# SP3485.net
KiCad netlist of a schematic drawn in Altium Designer
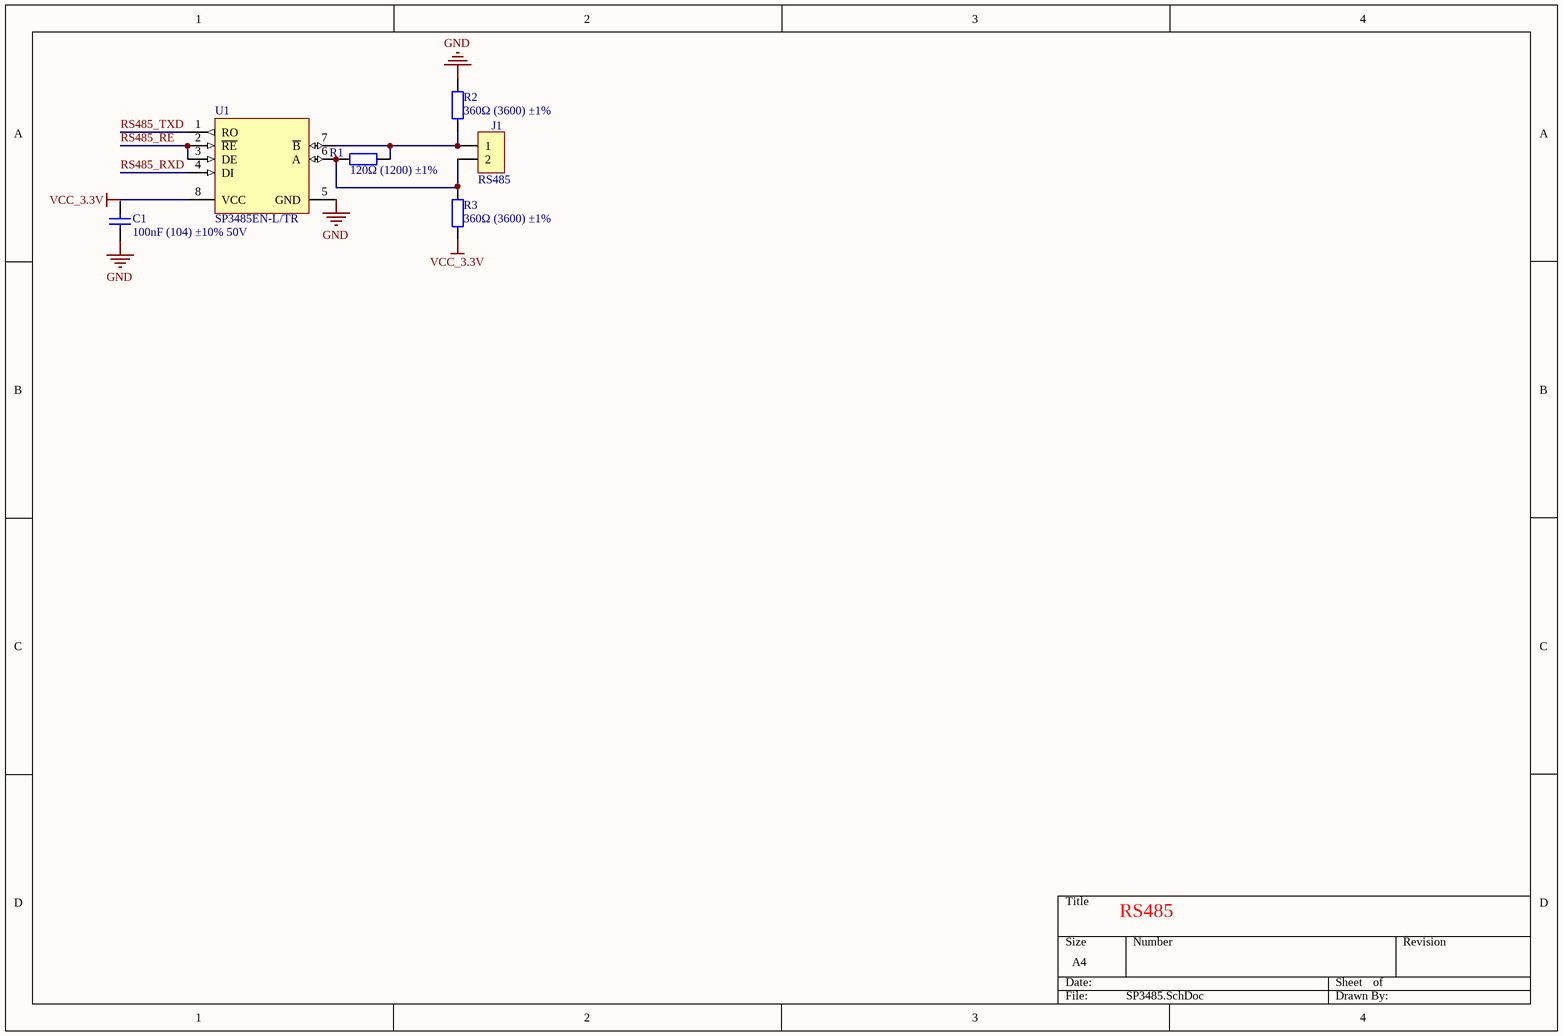
[diagram p0: SP3485.SchDoc]

(export (version "E")
  (design (tool "Eeschema 10.0.6"))
  (components
    (comp (ref "C1")
      (value "100nF (104) ±10% 50V")
      (footprint "CAPC_0603_2")
      (description "贴片电容")
      (libsource (lib "电容") (part "0603 100nF (104) ±10% 50V"))
    )
    (comp (ref "J1") (value "RS485") (description "2P接插件") (libsource (lib "接插件") (part "Header 2")))
    (comp (ref "R1")
      (value "120Ω (1200) ±1%")
      (footprint "RESC_0603_2")
      (description "贴片电阻")
      (libsource (lib "电阻") (part "0603 120Ω (1200) ±1%"))
    )
    (comp (ref "R2")
      (value "360Ω (3600) ±1%")
      (footprint "RESC_0603_2")
      (description "贴片电阻")
      (libsource (lib "电阻") (part "0603 360Ω (3600) ±1%"))
    )
    (comp (ref "R3")
      (value "360Ω (3600) ±1%")
      (footprint "RESC_0603_2")
      (description "贴片电阻")
      (libsource (lib "电阻") (part "0603 360Ω (3600) ±1%"))
    )
    (comp (ref "U1")
      (value "SP3485EN-L/TR")
      (footprint "SOIC_8")
      (description "RS-485/RS-422")
      (libsource (lib "IC") (part "SP3485EN-L/TR_[C8963]"))
    )
  )
  (nets
    (net (code "1") (name "/RS485_RE") (class "Default")
      (node (ref "U1") (pin "2") (pinfunction "~{RE}_2") (pintype "input"))
      (node (ref "U1") (pin "3") (pinfunction "DE_3") (pintype "input"))
    )
    (net (code "2") (name "/RS485_RXD") (class "Default")
      (node (ref "U1") (pin "4") (pinfunction "DI_4") (pintype "input"))
    )
    (net (code "3") (name "/RS485_TXD") (class "Default")
      (node (ref "U1") (pin "1") (pinfunction "RO_1") (pintype "output"))
    )
    (net (code "4") (name "GND") (class "Default")
      (node (ref "C1") (pin "1") (pinfunction "1_1") (pintype "passive"))
      (node (ref "R2") (pin "2") (pinfunction "2_2") (pintype "passive"))
      (node (ref "U1") (pin "5") (pinfunction "GND_5") (pintype "power_in"))
    )
    (net (code "5") (name "Net-(U1-A)") (class "Default")
      (node (ref "J1") (pin "2") (pinfunction "2_2") (pintype "passive"))
      (node (ref "R1") (pin "1") (pinfunction "1_1") (pintype "passive"))
      (node (ref "R3") (pin "2") (pinfunction "2_2") (pintype "passive"))
      (node (ref "U1") (pin "6") (pinfunction "A_6") (pintype "bidirectional"))
    )
    (net (code "6") (name "Net-(U1-~{B})") (class "Default")
      (node (ref "J1") (pin "1") (pinfunction "1_1") (pintype "passive"))
      (node (ref "R1") (pin "2") (pinfunction "2_2") (pintype "passive"))
      (node (ref "R2") (pin "1") (pinfunction "1_1") (pintype "passive"))
      (node (ref "U1") (pin "7") (pinfunction "~{B}_7") (pintype "bidirectional"))
    )
    (net (code "7") (name "VCC_3.3V") (class "Default")
      (node (ref "R3") (pin "1") (pinfunction "1_1") (pintype "passive"))
      (node (ref "U1") (pin "8") (pinfunction "VCC_8") (pintype "power_in"))
    )
    (net (code "8") (name "unconnected-(C1-Pad2)") (class "Default")
      (node (ref "C1") (pin "2") (pinfunction "2_2") (pintype "passive"))
    )
  )
)
